# temperature-led-r1.net
KiCad netlist of a schematic drawn in EAGLE
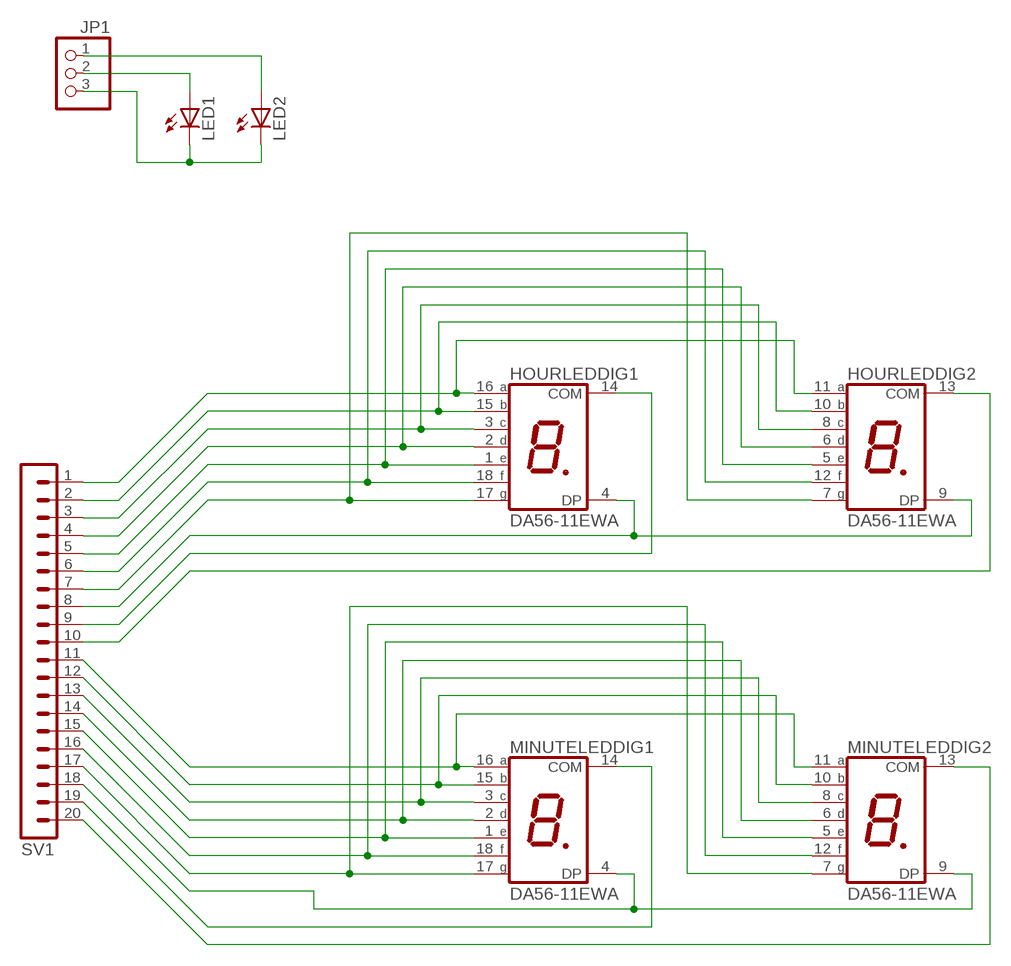
[diagram p0: schematic, sheet 1]

(export (version "E")
  (design (tool "Eeschema 10.0.6"))
  (components
    (comp (ref "HOURLED")
      (value "DA56-11EWA")
      (footprint "eagle-import:DA56")
      (libsource (lib "eagle-import") (part "DA56-11EWA"))
    )
    (comp (ref "JP1")
      (value "PINHD-1X3")
      (footprint "eagle-import:1X03")
      (libsource (lib "eagle-import") (part "PINHD-1X3"))
    )
    (comp (ref "LED1")
      (value "LED3MM")
      (footprint "eagle-import:LED3MM")
      (libsource (lib "eagle-import") (part "LED3MM"))
    )
    (comp (ref "LED2")
      (value "LED3MM")
      (footprint "eagle-import:LED3MM")
      (libsource (lib "eagle-import") (part "LED3MM"))
    )
    (comp (ref "MINUTELED")
      (value "DA56-11EWA")
      (footprint "eagle-import:DA56")
      (libsource (lib "eagle-import") (part "DA56-11EWA"))
    )
    (comp (ref "SV1")
      (value "MA20-1W")
      (footprint "eagle-import:MA20-1W")
      (libsource (lib "eagle-import") (part "MA20-1W"))
    )
  )
  (nets
    (net (code "1") (name "Net-(HOURLEDA-A)") (class "Default")
      (node (ref "HOURLED") (pin "11") (pinfunction "A_11") (pintype "passive"))
      (node (ref "HOURLED") (pin "16") (pinfunction "A_16") (pintype "passive"))
      (node (ref "SV1") (pin "1") (pinfunction "1_1") (pintype "passive"))
    )
    (net (code "2") (name "Net-(HOURLEDA-B)") (class "Default")
      (node (ref "HOURLED") (pin "10") (pinfunction "B_10") (pintype "passive"))
      (node (ref "HOURLED") (pin "15") (pinfunction "B_15") (pintype "passive"))
      (node (ref "SV1") (pin "2") (pinfunction "2_2") (pintype "passive"))
    )
    (net (code "3") (name "Net-(HOURLEDA-C)") (class "Default")
      (node (ref "HOURLED") (pin "3") (pinfunction "C_3") (pintype "passive"))
      (node (ref "HOURLED") (pin "8") (pinfunction "C_8") (pintype "passive"))
      (node (ref "SV1") (pin "3") (pinfunction "3_3") (pintype "passive"))
    )
    (net (code "4") (name "Net-(HOURLEDA-COM)") (class "Default")
      (node (ref "HOURLED") (pin "14") (pinfunction "COM_14") (pintype "passive"))
      (node (ref "SV1") (pin "9") (pinfunction "9_9") (pintype "passive"))
    )
    (net (code "5") (name "Net-(HOURLEDA-D)") (class "Default")
      (node (ref "HOURLED") (pin "2") (pinfunction "D_2") (pintype "passive"))
      (node (ref "HOURLED") (pin "6") (pinfunction "D_6") (pintype "passive"))
      (node (ref "SV1") (pin "4") (pinfunction "4_4") (pintype "passive"))
    )
    (net (code "6") (name "Net-(HOURLEDA-DP)") (class "Default")
      (node (ref "HOURLED") (pin "4") (pinfunction "DP_4") (pintype "passive"))
      (node (ref "HOURLED") (pin "9") (pinfunction "DP_9") (pintype "passive"))
      (node (ref "SV1") (pin "8") (pinfunction "8_8") (pintype "passive"))
    )
    (net (code "7") (name "Net-(HOURLEDA-E)") (class "Default")
      (node (ref "HOURLED") (pin "1") (pinfunction "E_1") (pintype "passive"))
      (node (ref "HOURLED") (pin "5") (pinfunction "E_5") (pintype "passive"))
      (node (ref "SV1") (pin "5") (pinfunction "5_5") (pintype "passive"))
    )
    (net (code "8") (name "Net-(HOURLEDA-F)") (class "Default")
      (node (ref "HOURLED") (pin "12") (pinfunction "F_12") (pintype "passive"))
      (node (ref "HOURLED") (pin "18") (pinfunction "F_18") (pintype "passive"))
      (node (ref "SV1") (pin "6") (pinfunction "6_6") (pintype "passive"))
    )
    (net (code "9") (name "Net-(HOURLEDA-G)") (class "Default")
      (node (ref "HOURLED") (pin "17") (pinfunction "G_17") (pintype "passive"))
      (node (ref "HOURLED") (pin "7") (pinfunction "G_7") (pintype "passive"))
      (node (ref "SV1") (pin "7") (pinfunction "7_7") (pintype "passive"))
    )
    (net (code "10") (name "Net-(HOURLEDB-COM)") (class "Default")
      (node (ref "HOURLED") (pin "13") (pinfunction "COM_13") (pintype "passive"))
      (node (ref "SV1") (pin "10") (pinfunction "10_10") (pintype "passive"))
    )
    (net (code "11") (name "Net-(JP1-Pad1)") (class "Default")
      (node (ref "JP1") (pin "1") (pinfunction "1_1") (pintype "passive"))
      (node (ref "LED2") (pin "A") (pinfunction "A_A") (pintype "passive"))
    )
    (net (code "12") (name "Net-(JP1-Pad2)") (class "Default")
      (node (ref "JP1") (pin "2") (pinfunction "2_2") (pintype "passive"))
      (node (ref "LED1") (pin "A") (pinfunction "A_A") (pintype "passive"))
    )
    (net (code "13") (name "Net-(LED1-C)") (class "Default")
      (node (ref "JP1") (pin "3") (pinfunction "3_3") (pintype "passive"))
      (node (ref "LED1") (pin "K") (pinfunction "C_K") (pintype "passive"))
      (node (ref "LED2") (pin "K") (pinfunction "C_K") (pintype "passive"))
    )
    (net (code "14") (name "Net-(MINUTELEDA-A)") (class "Default")
      (node (ref "MINUTELED") (pin "11") (pinfunction "A_11") (pintype "passive"))
      (node (ref "MINUTELED") (pin "16") (pinfunction "A_16") (pintype "passive"))
      (node (ref "SV1") (pin "11") (pinfunction "11_11") (pintype "passive"))
    )
    (net (code "15") (name "Net-(MINUTELEDA-B)") (class "Default")
      (node (ref "MINUTELED") (pin "10") (pinfunction "B_10") (pintype "passive"))
      (node (ref "MINUTELED") (pin "15") (pinfunction "B_15") (pintype "passive"))
      (node (ref "SV1") (pin "12") (pinfunction "12_12") (pintype "passive"))
    )
    (net (code "16") (name "Net-(MINUTELEDA-C)") (class "Default")
      (node (ref "MINUTELED") (pin "3") (pinfunction "C_3") (pintype "passive"))
      (node (ref "MINUTELED") (pin "8") (pinfunction "C_8") (pintype "passive"))
      (node (ref "SV1") (pin "13") (pinfunction "13_13") (pintype "passive"))
    )
    (net (code "17") (name "Net-(MINUTELEDA-COM)") (class "Default")
      (node (ref "MINUTELED") (pin "14") (pinfunction "COM_14") (pintype "passive"))
      (node (ref "SV1") (pin "19") (pinfunction "19_19") (pintype "passive"))
    )
    (net (code "18") (name "Net-(MINUTELEDA-D)") (class "Default")
      (node (ref "MINUTELED") (pin "2") (pinfunction "D_2") (pintype "passive"))
      (node (ref "MINUTELED") (pin "6") (pinfunction "D_6") (pintype "passive"))
      (node (ref "SV1") (pin "14") (pinfunction "14_14") (pintype "passive"))
    )
    (net (code "19") (name "Net-(MINUTELEDA-DP)") (class "Default")
      (node (ref "MINUTELED") (pin "4") (pinfunction "DP_4") (pintype "passive"))
      (node (ref "MINUTELED") (pin "9") (pinfunction "DP_9") (pintype "passive"))
      (node (ref "SV1") (pin "18") (pinfunction "18_18") (pintype "passive"))
    )
    (net (code "20") (name "Net-(MINUTELEDA-E)") (class "Default")
      (node (ref "MINUTELED") (pin "1") (pinfunction "E_1") (pintype "passive"))
      (node (ref "MINUTELED") (pin "5") (pinfunction "E_5") (pintype "passive"))
      (node (ref "SV1") (pin "15") (pinfunction "15_15") (pintype "passive"))
    )
    (net (code "21") (name "Net-(MINUTELEDA-F)") (class "Default")
      (node (ref "MINUTELED") (pin "12") (pinfunction "F_12") (pintype "passive"))
      (node (ref "MINUTELED") (pin "18") (pinfunction "F_18") (pintype "passive"))
      (node (ref "SV1") (pin "16") (pinfunction "16_16") (pintype "passive"))
    )
    (net (code "22") (name "Net-(MINUTELEDA-G)") (class "Default")
      (node (ref "MINUTELED") (pin "17") (pinfunction "G_17") (pintype "passive"))
      (node (ref "MINUTELED") (pin "7") (pinfunction "G_7") (pintype "passive"))
      (node (ref "SV1") (pin "17") (pinfunction "17_17") (pintype "passive"))
    )
    (net (code "23") (name "Net-(MINUTELEDB-COM)") (class "Default")
      (node (ref "MINUTELED") (pin "13") (pinfunction "COM_13") (pintype "passive"))
      (node (ref "SV1") (pin "20") (pinfunction "20_20") (pintype "passive"))
    )
  )
)
